# astable_multivibrator.net
KiCad netlist of a schematic drawn in EAGLE
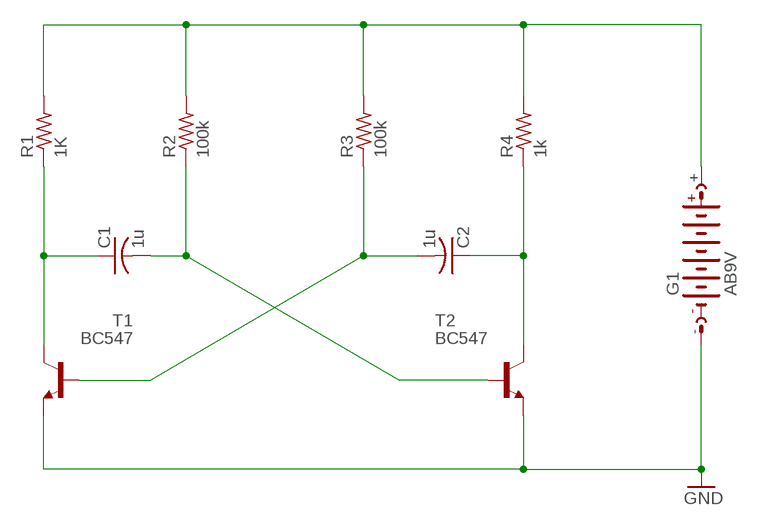
[diagram p0: schematic, sheet 1]

(export (version "E")
  (design (tool "Eeschema 10.0.6"))
  (components
    (comp (ref "C1")
      (value "1u")
      (footprint "eagle-import:C0805")
      (libsource (lib "eagle-import") (part "C-USC0805"))
    )
    (comp (ref "C2")
      (value "1u")
      (footprint "eagle-import:C0805")
      (libsource (lib "eagle-import") (part "C-USC0805"))
    )
    (comp (ref "G1")
      (value "AB9V")
      (footprint "eagle-import:AB9V")
      (libsource (lib "eagle-import") (part "AB9V"))
    )
    (comp (ref "R1")
      (value "1K")
      (footprint "eagle-import:R0805")
      (libsource (lib "eagle-import") (part "R-US_R0805"))
    )
    (comp (ref "R2")
      (value "100k")
      (footprint "eagle-import:R0805")
      (libsource (lib "eagle-import") (part "R-US_R0805"))
    )
    (comp (ref "R3")
      (value "100k")
      (footprint "eagle-import:R0805")
      (libsource (lib "eagle-import") (part "R-US_R0805"))
    )
    (comp (ref "R4")
      (value "1k")
      (footprint "eagle-import:R0805")
      (libsource (lib "eagle-import") (part "R-US_R0805"))
    )
    (comp (ref "T1")
      (value "BC547")
      (footprint "eagle-import:TO92")
      (libsource (lib "eagle-import") (part "BC547"))
    )
    (comp (ref "T2")
      (value "BC547")
      (footprint "eagle-import:TO92")
      (libsource (lib "eagle-import") (part "BC547"))
    )
  )
  (nets
    (net (code "1") (name "GND") (class "Default")
      (node (ref "G1") (pin "-") (pinfunction "-_-") (pintype "passive"))
      (node (ref "T1") (pin "1") (pinfunction "E_1") (pintype "passive"))
      (node (ref "T2") (pin "1") (pinfunction "E_1") (pintype "passive"))
    )
    (net (code "2") (name "Net-(G1-Pad+)") (class "Default")
      (node (ref "G1") (pin "+") (pinfunction "+_+") (pintype "passive"))
      (node (ref "R1") (pin "2") (pinfunction "2_2") (pintype "passive"))
      (node (ref "R2") (pin "2") (pinfunction "2_2") (pintype "passive"))
      (node (ref "R3") (pin "2") (pinfunction "2_2") (pintype "passive"))
      (node (ref "R4") (pin "2") (pinfunction "2_2") (pintype "passive"))
    )
    (net (code "3") (name "Net-(T1-B)") (class "Default")
      (node (ref "C2") (pin "2") (pinfunction "2_2") (pintype "passive"))
      (node (ref "R3") (pin "1") (pinfunction "1_1") (pintype "passive"))
      (node (ref "T1") (pin "2") (pinfunction "B_2") (pintype "passive"))
    )
    (net (code "4") (name "Net-(T1-C)") (class "Default")
      (node (ref "C1") (pin "1") (pinfunction "1_1") (pintype "passive"))
      (node (ref "R1") (pin "1") (pinfunction "1_1") (pintype "passive"))
      (node (ref "T1") (pin "3") (pinfunction "C_3") (pintype "passive"))
    )
    (net (code "5") (name "Net-(T2-B)") (class "Default")
      (node (ref "C1") (pin "2") (pinfunction "2_2") (pintype "passive"))
      (node (ref "R2") (pin "1") (pinfunction "1_1") (pintype "passive"))
      (node (ref "T2") (pin "2") (pinfunction "B_2") (pintype "passive"))
    )
    (net (code "6") (name "Net-(T2-C)") (class "Default")
      (node (ref "C2") (pin "1") (pinfunction "1_1") (pintype "passive"))
      (node (ref "R4") (pin "1") (pinfunction "1_1") (pintype "passive"))
      (node (ref "T2") (pin "3") (pinfunction "C_3") (pintype "passive"))
    )
  )
)
